# CAN.net
KiCad netlist of a schematic drawn in Altium Designer
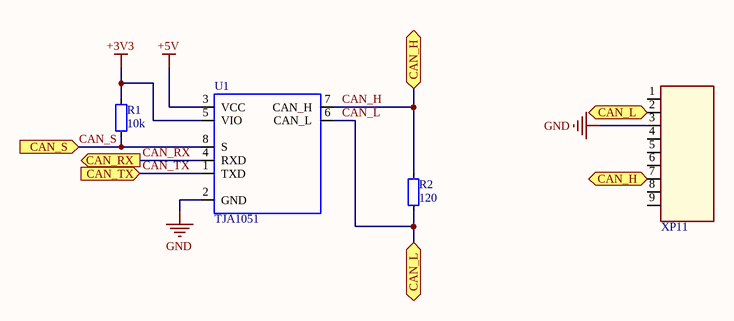
[diagram p0: CAN.SchDoc]

(export (version "E")
  (design (tool "Eeschema 10.0.6"))
  (components
    (comp (ref "R1")
      (value "10k")
      (footprint "DISCRETE:SMD_0603")
      (description "Resistor")
      (libsource (lib "DISCRETE") (part "RES"))
    )
    (comp (ref "R2")
      (value "120")
      (footprint "DISCRETE:SMD_0603")
      (description "Resistor")
      (libsource (lib "DISCRETE") (part "RES"))
    )
    (comp (ref "U1") (value "TJA1051") (footprint "ICs:SO8-150mil") (libsource (lib "ICs") (part "TJA1051")))
    (comp (ref "XP11")
      (value "DB9M_CABLE")
      (footprint "Connectors:DSUB-9_M_Edge")
      (libsource (lib "Connectors") (part "DB9F_EDGE"))
    )
  )
  (nets
    (net (code "1") (name "+3V3") (class "Default")
      (node (ref "R1") (pin "2") (pintype "passive"))
      (node (ref "U1") (pin "5") (pinfunction "VIO_5") (pintype "passive"))
    )
    (net (code "2") (name "+5V") (class "Default")
      (node (ref "U1") (pin "3") (pinfunction "VCC_3") (pintype "passive"))
    )
    (net (code "3") (name "/CAN_H") (class "Default")
      (node (ref "R2") (pin "2") (pintype "passive"))
      (node (ref "U1") (pin "7") (pinfunction "CAN_H_7") (pintype "passive"))
      (node (ref "XP11") (pin "7") (pinfunction "7_7") (pintype "passive"))
    )
    (net (code "4") (name "/CAN_L") (class "Default")
      (node (ref "R2") (pin "1") (pintype "passive"))
      (node (ref "U1") (pin "6") (pinfunction "CAN_L_6") (pintype "passive"))
      (node (ref "XP11") (pin "2") (pinfunction "2_2") (pintype "passive"))
    )
    (net (code "5") (name "/CAN_RX") (class "Default")
      (node (ref "U1") (pin "4") (pinfunction "RXD_4") (pintype "passive"))
    )
    (net (code "6") (name "/CAN_S") (class "Default")
      (node (ref "R1") (pin "1") (pintype "passive"))
      (node (ref "U1") (pin "8") (pinfunction "S_8") (pintype "passive"))
    )
    (net (code "7") (name "/CAN_TX") (class "Default")
      (node (ref "U1") (pin "1") (pinfunction "TXD_1") (pintype "passive"))
    )
    (net (code "8") (name "GND") (class "Default")
      (node (ref "U1") (pin "2") (pinfunction "GND_2") (pintype "passive"))
      (node (ref "XP11") (pin "3") (pinfunction "3_3") (pintype "passive"))
    )
    (net (code "9") (name "unconnected-(XP11-Pad1)") (class "Default")
      (node (ref "XP11") (pin "1") (pinfunction "1_1") (pintype "passive"))
    )
    (net (code "10") (name "unconnected-(XP11-Pad4)") (class "Default")
      (node (ref "XP11") (pin "4") (pinfunction "4_4") (pintype "passive"))
    )
    (net (code "11") (name "unconnected-(XP11-Pad5)") (class "Default")
      (node (ref "XP11") (pin "5") (pinfunction "5_5") (pintype "passive"))
    )
    (net (code "12") (name "unconnected-(XP11-Pad6)") (class "Default")
      (node (ref "XP11") (pin "6") (pinfunction "6_6") (pintype "passive"))
    )
    (net (code "13") (name "unconnected-(XP11-Pad8)") (class "Default")
      (node (ref "XP11") (pin "8") (pinfunction "8_8") (pintype "passive"))
    )
    (net (code "14") (name "unconnected-(XP11-Pad9)") (class "Default")
      (node (ref "XP11") (pin "9") (pinfunction "9_9") (pintype "passive"))
    )
  )
)
